# Interface_EPROM_Kte.net
KiCad netlist of a schematic drawn in EAGLE
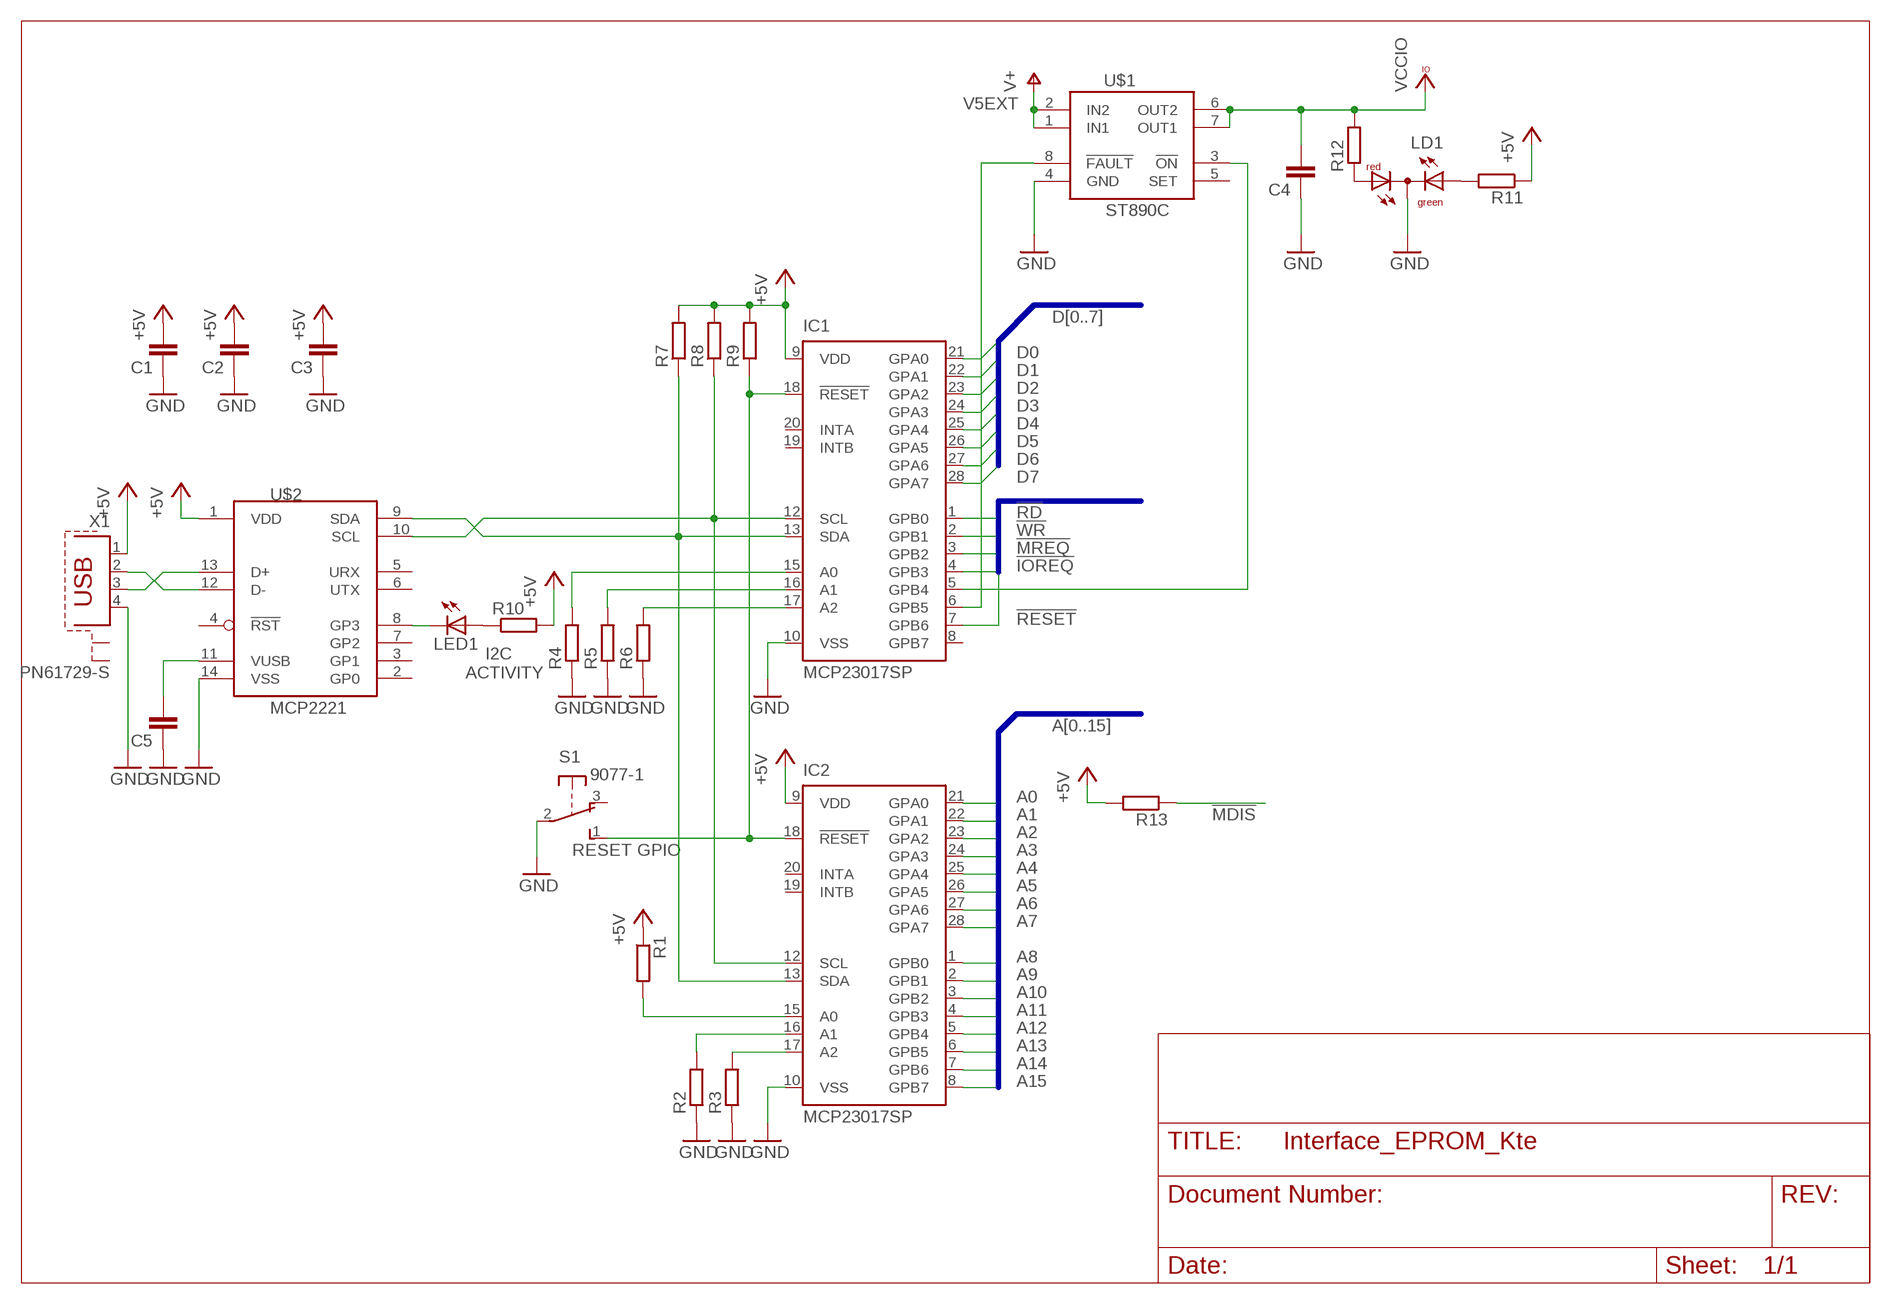
[diagram p0: schematic, sheet 1]

(export (version "E")
  (design (tool "Eeschema 10.0.6"))
  (components
    (comp (ref "C1")
      (value "C-EUC0805")
      (footprint "eagle-import:C0805")
      (libsource (lib "eagle-import") (part "C-EUC0805"))
    )
    (comp (ref "C2")
      (value "C-EUC0805")
      (footprint "eagle-import:C0805")
      (libsource (lib "eagle-import") (part "C-EUC0805"))
    )
    (comp (ref "C3")
      (value "C-EUC0805")
      (footprint "eagle-import:C0805")
      (libsource (lib "eagle-import") (part "C-EUC0805"))
    )
    (comp (ref "C4")
      (value "C-EUC0805")
      (footprint "eagle-import:C0805")
      (libsource (lib "eagle-import") (part "C-EUC0805"))
    )
    (comp (ref "C5")
      (value "C-EUC0805")
      (footprint "eagle-import:C0805")
      (libsource (lib "eagle-import") (part "C-EUC0805"))
    )
    (comp (ref "IC1")
      (value "MCP23017SP")
      (footprint "eagle-import:DIL28-3")
      (fields (field (name "MF") "MICROCHIP") (field (name "MPN") "MCP23017-E/SP"))
      (libsource (lib "eagle-import") (part "MCP23017SP"))
    )
    (comp (ref "IC2")
      (value "MCP23017SP")
      (footprint "eagle-import:DIL28-3")
      (fields (field (name "MF") "MICROCHIP") (field (name "MPN") "MCP23017-E/SP"))
      (libsource (lib "eagle-import") (part "MCP23017SP"))
    )
    (comp (ref "LD1")
      (value "DUOLED-RG-C")
      (footprint "eagle-import:DUOLED-C-5MM")
      (libsource (lib "eagle-import") (part "DUOLED-RG-C"))
    )
    (comp (ref "LED1")
      (value "LED3MM")
      (footprint "eagle-import:LED3MM")
      (libsource (lib "eagle-import") (part "LED3MM"))
    )
    (comp (ref "R1")
      (value "R-EU_R0805")
      (footprint "eagle-import:R0805")
      (libsource (lib "eagle-import") (part "R-EU_R0805"))
    )
    (comp (ref "R2")
      (value "R-EU_R0805")
      (footprint "eagle-import:R0805")
      (libsource (lib "eagle-import") (part "R-EU_R0805"))
    )
    (comp (ref "R3")
      (value "R-EU_R0805")
      (footprint "eagle-import:R0805")
      (libsource (lib "eagle-import") (part "R-EU_R0805"))
    )
    (comp (ref "R4")
      (value "R-EU_R0805")
      (footprint "eagle-import:R0805")
      (libsource (lib "eagle-import") (part "R-EU_R0805"))
    )
    (comp (ref "R5")
      (value "R-EU_R0805")
      (footprint "eagle-import:R0805")
      (libsource (lib "eagle-import") (part "R-EU_R0805"))
    )
    (comp (ref "R6")
      (value "R-EU_R0805")
      (footprint "eagle-import:R0805")
      (libsource (lib "eagle-import") (part "R-EU_R0805"))
    )
    (comp (ref "R7")
      (value "R-EU_R0805")
      (footprint "eagle-import:R0805")
      (libsource (lib "eagle-import") (part "R-EU_R0805"))
    )
    (comp (ref "R8")
      (value "R-EU_R0805")
      (footprint "eagle-import:R0805")
      (libsource (lib "eagle-import") (part "R-EU_R0805"))
    )
    (comp (ref "R9")
      (value "R-EU_R0805")
      (footprint "eagle-import:R0805")
      (libsource (lib "eagle-import") (part "R-EU_R0805"))
    )
    (comp (ref "R10")
      (value "R-EU_R0805")
      (footprint "eagle-import:R0805")
      (libsource (lib "eagle-import") (part "R-EU_R0805"))
    )
    (comp (ref "R11")
      (value "R-EU_R0805")
      (footprint "eagle-import:R0805")
      (libsource (lib "eagle-import") (part "R-EU_R0805"))
    )
    (comp (ref "R12")
      (value "R-EU_R0805")
      (footprint "eagle-import:R0805")
      (libsource (lib "eagle-import") (part "R-EU_R0805"))
    )
    (comp (ref "R13")
      (value "R-EU_R0805")
      (footprint "eagle-import:R0805")
      (libsource (lib "eagle-import") (part "R-EU_R0805"))
    )
    (comp (ref "S1")
      (value "9077-1")
      (footprint "eagle-import:9077-1")
      (libsource (lib "eagle-import") (part "9077-1"))
    )
    (comp (ref "U$1")
      (value "ST890C")
      (footprint "eagle-import:SO-08")
      (libsource (lib "eagle-import") (part "ST890C"))
    )
    (comp (ref "U$2")
      (value "MCP2221")
      (footprint "eagle-import:DIL14")
      (libsource (lib "eagle-import") (part "MCP2221"))
    )
    (comp (ref "X1")
      (value "PN61729-S")
      (footprint "eagle-import:PN61729-S")
      (libsource (lib "eagle-import") (part "PN61729-S"))
    )
  )
  (nets
    (net (code "1") (name "+5V") (class "Default")
      (node (ref "C1") (pin "2") (pinfunction "2_2") (pintype "passive"))
      (node (ref "C2") (pin "2") (pinfunction "2_2") (pintype "passive"))
      (node (ref "C3") (pin "2") (pinfunction "2_2") (pintype "passive"))
      (node (ref "IC1") (pin "9") (pinfunction "VDD_9") (pintype "power_in"))
      (node (ref "IC2") (pin "9") (pinfunction "VDD_9") (pintype "power_in"))
      (node (ref "R1") (pin "1") (pinfunction "1_1") (pintype "passive"))
      (node (ref "R10") (pin "2") (pinfunction "2_2") (pintype "passive"))
      (node (ref "R11") (pin "1") (pinfunction "1_1") (pintype "passive"))
      (node (ref "R13") (pin "2") (pinfunction "2_2") (pintype "passive"))
      (node (ref "R7") (pin "2") (pinfunction "2_2") (pintype "passive"))
      (node (ref "R8") (pin "2") (pinfunction "2_2") (pintype "passive"))
      (node (ref "R9") (pin "2") (pinfunction "2_2") (pintype "passive"))
      (node (ref "U$2") (pin "1") (pinfunction "VDD_1") (pintype "power_in"))
      (node (ref "X1") (pin "1") (pinfunction "1_1") (pintype "passive"))
    )
    (net (code "26") (name "/A0") (class "Default")
      (node (ref "IC2") (pin "21") (pinfunction "GPA0_21") (pintype "bidirectional"))
    )
    (net (code "29") (name "/A1") (class "Default")
      (node (ref "IC2") (pin "22") (pinfunction "GPA1_22") (pintype "bidirectional"))
    )
    (net (code "31") (name "/A2") (class "Default")
      (node (ref "IC2") (pin "23") (pinfunction "GPA2_23") (pintype "bidirectional"))
    )
    (net (code "32") (name "/A3") (class "Default")
      (node (ref "IC2") (pin "24") (pinfunction "GPA3_24") (pintype "bidirectional"))
    )
    (net (code "33") (name "/A4") (class "Default")
      (node (ref "IC2") (pin "25") (pinfunction "GPA4_25") (pintype "bidirectional"))
    )
    (net (code "34") (name "/A5") (class "Default")
      (node (ref "IC2") (pin "26") (pinfunction "GPA5_26") (pintype "bidirectional"))
    )
    (net (code "35") (name "/A6") (class "Default")
      (node (ref "IC2") (pin "27") (pinfunction "GPA6_27") (pintype "bidirectional"))
    )
    (net (code "36") (name "/A7") (class "Default")
      (node (ref "IC2") (pin "28") (pinfunction "GPA7_28") (pintype "bidirectional"))
    )
    (net (code "37") (name "/A8") (class "Default")
      (node (ref "IC2") (pin "1") (pinfunction "GPB0_1") (pintype "bidirectional"))
    )
    (net (code "38") (name "/A9") (class "Default")
      (node (ref "IC2") (pin "2") (pinfunction "GPB1_2") (pintype "bidirectional"))
    )
    (net (code "39") (name "/A10") (class "Default")
      (node (ref "IC2") (pin "3") (pinfunction "GPB2_3") (pintype "bidirectional"))
    )
    (net (code "40") (name "/A11") (class "Default")
      (node (ref "IC2") (pin "4") (pinfunction "GPB3_4") (pintype "bidirectional"))
    )
    (net (code "41") (name "/A12") (class "Default")
      (node (ref "IC2") (pin "5") (pinfunction "GPB4_5") (pintype "bidirectional"))
    )
    (net (code "42") (name "/A13") (class "Default")
      (node (ref "IC2") (pin "6") (pinfunction "GPB5_6") (pintype "bidirectional"))
    )
    (net (code "43") (name "/A14") (class "Default")
      (node (ref "IC2") (pin "7") (pinfunction "GPB6_7") (pintype "bidirectional"))
    )
    (net (code "44") (name "/A15") (class "Default")
      (node (ref "IC2") (pin "8") (pinfunction "GPB7_8") (pintype "bidirectional"))
    )
    (net (code "45") (name "/D0") (class "Default")
      (node (ref "IC1") (pin "21") (pinfunction "GPA0_21") (pintype "bidirectional"))
    )
    (net (code "46") (name "/D1") (class "Default")
      (node (ref "IC1") (pin "22") (pinfunction "GPA1_22") (pintype "bidirectional"))
    )
    (net (code "47") (name "/D2") (class "Default")
      (node (ref "IC1") (pin "23") (pinfunction "GPA2_23") (pintype "bidirectional"))
    )
    (net (code "48") (name "/D3") (class "Default")
      (node (ref "IC1") (pin "24") (pinfunction "GPA3_24") (pintype "bidirectional"))
    )
    (net (code "49") (name "/D4") (class "Default")
      (node (ref "IC1") (pin "25") (pinfunction "GPA4_25") (pintype "bidirectional"))
    )
    (net (code "50") (name "/D5") (class "Default")
      (node (ref "IC1") (pin "26") (pinfunction "GPA5_26") (pintype "bidirectional"))
    )
    (net (code "51") (name "/D6") (class "Default")
      (node (ref "IC1") (pin "27") (pinfunction "GPA6_27") (pintype "bidirectional"))
    )
    (net (code "52") (name "/D7") (class "Default")
      (node (ref "IC1") (pin "28") (pinfunction "GPA7_28") (pintype "bidirectional"))
    )
    (net (code "53") (name "/~{IOREQ}") (class "Default")
      (node (ref "IC1") (pin "4") (pinfunction "GPB3_4") (pintype "bidirectional"))
    )
    (net (code "54") (name "/~{MDIS}") (class "Default")
      (node (ref "R13") (pin "1") (pinfunction "1_1") (pintype "passive"))
    )
    (net (code "55") (name "/~{MREQ}") (class "Default")
      (node (ref "IC1") (pin "3") (pinfunction "GPB2_3") (pintype "bidirectional"))
    )
    (net (code "56") (name "/~{RD}") (class "Default")
      (node (ref "IC1") (pin "1") (pinfunction "GPB0_1") (pintype "bidirectional"))
    )
    (net (code "57") (name "/~{RESET}") (class "Default")
      (node (ref "IC1") (pin "7") (pinfunction "GPB6_7") (pintype "bidirectional"))
    )
    (net (code "58") (name "/~{WR}") (class "Default")
      (node (ref "IC1") (pin "2") (pinfunction "GPB1_2") (pintype "bidirectional"))
    )
    (net (code "59") (name "GND") (class "Default")
      (node (ref "C1") (pin "1") (pinfunction "1_1") (pintype "passive"))
      (node (ref "C2") (pin "1") (pinfunction "1_1") (pintype "passive"))
      (node (ref "C3") (pin "1") (pinfunction "1_1") (pintype "passive"))
      (node (ref "C4") (pin "1") (pinfunction "1_1") (pintype "passive"))
      (node (ref "C5") (pin "1") (pinfunction "1_1") (pintype "passive"))
      (node (ref "IC1") (pin "10") (pinfunction "VSS_10") (pintype "power_in"))
      (node (ref "IC2") (pin "10") (pinfunction "VSS_10") (pintype "power_in"))
      (node (ref "LD1") (pin "C") (pinfunction "C_C") (pintype "passive"))
      (node (ref "R2") (pin "1") (pinfunction "1_1") (pintype "passive"))
      (node (ref "R3") (pin "1") (pinfunction "1_1") (pintype "passive"))
      (node (ref "R4") (pin "1") (pinfunction "1_1") (pintype "passive"))
      (node (ref "R5") (pin "1") (pinfunction "1_1") (pintype "passive"))
      (node (ref "R6") (pin "1") (pinfunction "1_1") (pintype "passive"))
      (node (ref "S1") (pin "2") (pinfunction "P_2") (pintype "passive"))
      (node (ref "U$1") (pin "4") (pinfunction "GND_4") (pintype "bidirectional"))
      (node (ref "U$2") (pin "14") (pinfunction "VSS_14") (pintype "power_in"))
      (node (ref "X1") (pin "4") (pinfunction "4_4") (pintype "passive"))
    )
    (net (code "60") (name "Net-(IC1-A0)") (class "Default")
      (node (ref "IC1") (pin "15") (pinfunction "A0_15") (pintype "input"))
      (node (ref "R4") (pin "2") (pinfunction "2_2") (pintype "passive"))
    )
    (net (code "61") (name "Net-(IC1-A1)") (class "Default")
      (node (ref "IC1") (pin "16") (pinfunction "A1_16") (pintype "input"))
      (node (ref "R5") (pin "2") (pinfunction "2_2") (pintype "passive"))
    )
    (net (code "62") (name "Net-(IC1-A2)") (class "Default")
      (node (ref "IC1") (pin "17") (pinfunction "A2_17") (pintype "input"))
      (node (ref "R6") (pin "2") (pinfunction "2_2") (pintype "passive"))
    )
    (net (code "63") (name "Net-(IC1-GPB4)") (class "Default")
      (node (ref "IC1") (pin "5") (pinfunction "GPB4_5") (pintype "bidirectional"))
      (node (ref "U$1") (pin "3") (pinfunction "~{ON}_3") (pintype "bidirectional"))
    )
    (net (code "64") (name "Net-(IC1-GPB5)") (class "Default")
      (node (ref "IC1") (pin "6") (pinfunction "GPB5_6") (pintype "bidirectional"))
      (node (ref "U$1") (pin "8") (pinfunction "~{FAULT}_8") (pintype "bidirectional"))
    )
    (net (code "65") (name "Net-(IC1-SCL)") (class "Default")
      (node (ref "IC1") (pin "12") (pinfunction "SCL_12") (pintype "input"))
      (node (ref "IC2") (pin "12") (pinfunction "SCL_12") (pintype "input"))
      (node (ref "R8") (pin "1") (pinfunction "1_1") (pintype "passive"))
      (node (ref "U$2") (pin "10") (pinfunction "SCL_10") (pintype "output"))
    )
    (net (code "66") (name "Net-(IC1-SDA)") (class "Default")
      (node (ref "IC1") (pin "13") (pinfunction "SDA_13") (pintype "bidirectional"))
      (node (ref "IC2") (pin "13") (pinfunction "SDA_13") (pintype "bidirectional"))
      (node (ref "R7") (pin "1") (pinfunction "1_1") (pintype "passive"))
      (node (ref "U$2") (pin "9") (pinfunction "SDA_9") (pintype "bidirectional"))
    )
    (net (code "67") (name "Net-(IC1-~{RESET})") (class "Default")
      (node (ref "IC1") (pin "18") (pinfunction "~{RESET}_18") (pintype "input"))
      (node (ref "IC2") (pin "18") (pinfunction "~{RESET}_18") (pintype "input"))
      (node (ref "R9") (pin "1") (pinfunction "1_1") (pintype "passive"))
      (node (ref "S1") (pin "1") (pinfunction "S_1") (pintype "passive"))
    )
    (net (code "68") (name "Net-(IC2-A0)") (class "Default")
      (node (ref "IC2") (pin "15") (pinfunction "A0_15") (pintype "input"))
      (node (ref "R1") (pin "2") (pinfunction "2_2") (pintype "passive"))
    )
    (net (code "69") (name "Net-(IC2-A1)") (class "Default")
      (node (ref "IC2") (pin "16") (pinfunction "A1_16") (pintype "input"))
      (node (ref "R2") (pin "2") (pinfunction "2_2") (pintype "passive"))
    )
    (net (code "70") (name "Net-(IC2-A2)") (class "Default")
      (node (ref "IC2") (pin "17") (pinfunction "A2_17") (pintype "input"))
      (node (ref "R3") (pin "2") (pinfunction "2_2") (pintype "passive"))
    )
    (net (code "71") (name "Net-(LD1-AG)") (class "Default")
      (node (ref "LD1") (pin "AX") (pinfunction "AG_AX") (pintype "passive"))
      (node (ref "R11") (pin "2") (pinfunction "2_2") (pintype "passive"))
    )
    (net (code "72") (name "Net-(LD1-PadAR)") (class "Default")
      (node (ref "LD1") (pin "AR") (pinfunction "AR_AR") (pintype "passive"))
      (node (ref "R12") (pin "1") (pinfunction "1_1") (pintype "passive"))
    )
    (net (code "73") (name "Net-(LED1-C)") (class "Default")
      (node (ref "LED1") (pin "K") (pinfunction "C_K") (pintype "passive"))
      (node (ref "U$2") (pin "8") (pinfunction "GP3_8") (pintype "bidirectional"))
    )
    (net (code "74") (name "Net-(LED1-PadA)") (class "Default")
      (node (ref "LED1") (pin "A") (pinfunction "A_A") (pintype "passive"))
      (node (ref "R10") (pin "1") (pinfunction "1_1") (pintype "passive"))
    )
    (net (code "75") (name "Net-(U$2-D+)") (class "Default")
      (node (ref "U$2") (pin "13") (pinfunction "D+_13") (pintype "bidirectional"))
      (node (ref "X1") (pin "3") (pinfunction "3_3") (pintype "passive"))
    )
    (net (code "76") (name "Net-(U$2-D-)") (class "Default")
      (node (ref "U$2") (pin "12") (pinfunction "D-_12") (pintype "bidirectional"))
      (node (ref "X1") (pin "2") (pinfunction "2_2") (pintype "passive"))
    )
    (net (code "77") (name "Net-(U$2-VUSB)") (class "Default")
      (node (ref "C5") (pin "2") (pinfunction "2_2") (pintype "passive"))
      (node (ref "U$2") (pin "11") (pinfunction "VUSB_11") (pintype "power_in"))
    )
    (net (code "78") (name "V+") (class "Default")
      (node (ref "U$1") (pin "1") (pinfunction "IN1_1") (pintype "bidirectional"))
      (node (ref "U$1") (pin "2") (pinfunction "IN2_2") (pintype "bidirectional"))
    )
    (net (code "79") (name "VCCIO") (class "Default")
      (node (ref "C4") (pin "2") (pinfunction "2_2") (pintype "passive"))
      (node (ref "R12") (pin "2") (pinfunction "2_2") (pintype "passive"))
      (node (ref "U$1") (pin "6") (pinfunction "OUT2_6") (pintype "bidirectional"))
      (node (ref "U$1") (pin "7") (pinfunction "OUT1_7") (pintype "bidirectional"))
    )
    (net (code "80") (name "unconnected-(IC1-GPB7-Pad8)") (class "Default")
      (node (ref "IC1") (pin "8") (pinfunction "GPB7_8") (pintype "bidirectional"))
    )
    (net (code "81") (name "unconnected-(IC1-INTA-Pad20)") (class "Default")
      (node (ref "IC1") (pin "20") (pinfunction "INTA_20") (pintype "output"))
    )
    (net (code "82") (name "unconnected-(IC1-INTB-Pad19)") (class "Default")
      (node (ref "IC1") (pin "19") (pinfunction "INTB_19") (pintype "output"))
    )
    (net (code "83") (name "unconnected-(IC2-INTA-Pad20)") (class "Default")
      (node (ref "IC2") (pin "20") (pinfunction "INTA_20") (pintype "output"))
    )
    (net (code "84") (name "unconnected-(IC2-INTB-Pad19)") (class "Default")
      (node (ref "IC2") (pin "19") (pinfunction "INTB_19") (pintype "output"))
    )
    (net (code "85") (name "unconnected-(S1-O-Pad3)") (class "Default")
      (node (ref "S1") (pin "3") (pinfunction "O_3") (pintype "passive"))
    )
    (net (code "86") (name "unconnected-(U$1-SET-Pad5)") (class "Default")
      (node (ref "U$1") (pin "5") (pinfunction "SET_5") (pintype "bidirectional"))
    )
    (net (code "87") (name "unconnected-(U$2-GP0-Pad2)") (class "Default")
      (node (ref "U$2") (pin "2") (pinfunction "GP0_2") (pintype "bidirectional"))
    )
    (net (code "88") (name "unconnected-(U$2-GP1-Pad3)") (class "Default")
      (node (ref "U$2") (pin "3") (pinfunction "GP1_3") (pintype "bidirectional"))
    )
    (net (code "89") (name "unconnected-(U$2-GP2-Pad7)") (class "Default")
      (node (ref "U$2") (pin "7") (pinfunction "GP2_7") (pintype "bidirectional"))
    )
    (net (code "90") (name "unconnected-(U$2-URX-Pad5)") (class "Default")
      (node (ref "U$2") (pin "5") (pinfunction "URX_5") (pintype "input"))
    )
    (net (code "91") (name "unconnected-(U$2-UTX-Pad6)") (class "Default")
      (node (ref "U$2") (pin "6") (pinfunction "UTX_6") (pintype "output"))
    )
    (net (code "92") (name "unconnected-(U$2-~{RST}-Pad4)") (class "Default")
      (node (ref "U$2") (pin "4") (pinfunction "~{RST}_4") (pintype "input"))
    )
    (net (code "93") (name "unconnected-(X1-PadS1)") (class "Default")
      (node (ref "X1") (pin "S1") (pinfunction "S1_S1") (pintype "passive"))
    )
    (net (code "94") (name "unconnected-(X1-PadS2)") (class "Default")
      (node (ref "X1") (pin "S2") (pinfunction "S2_S2") (pintype "passive"))
    )
  )
)
